# Peripheral_Circuit_B.net
KiCad netlist of a schematic drawn in Altium Designer
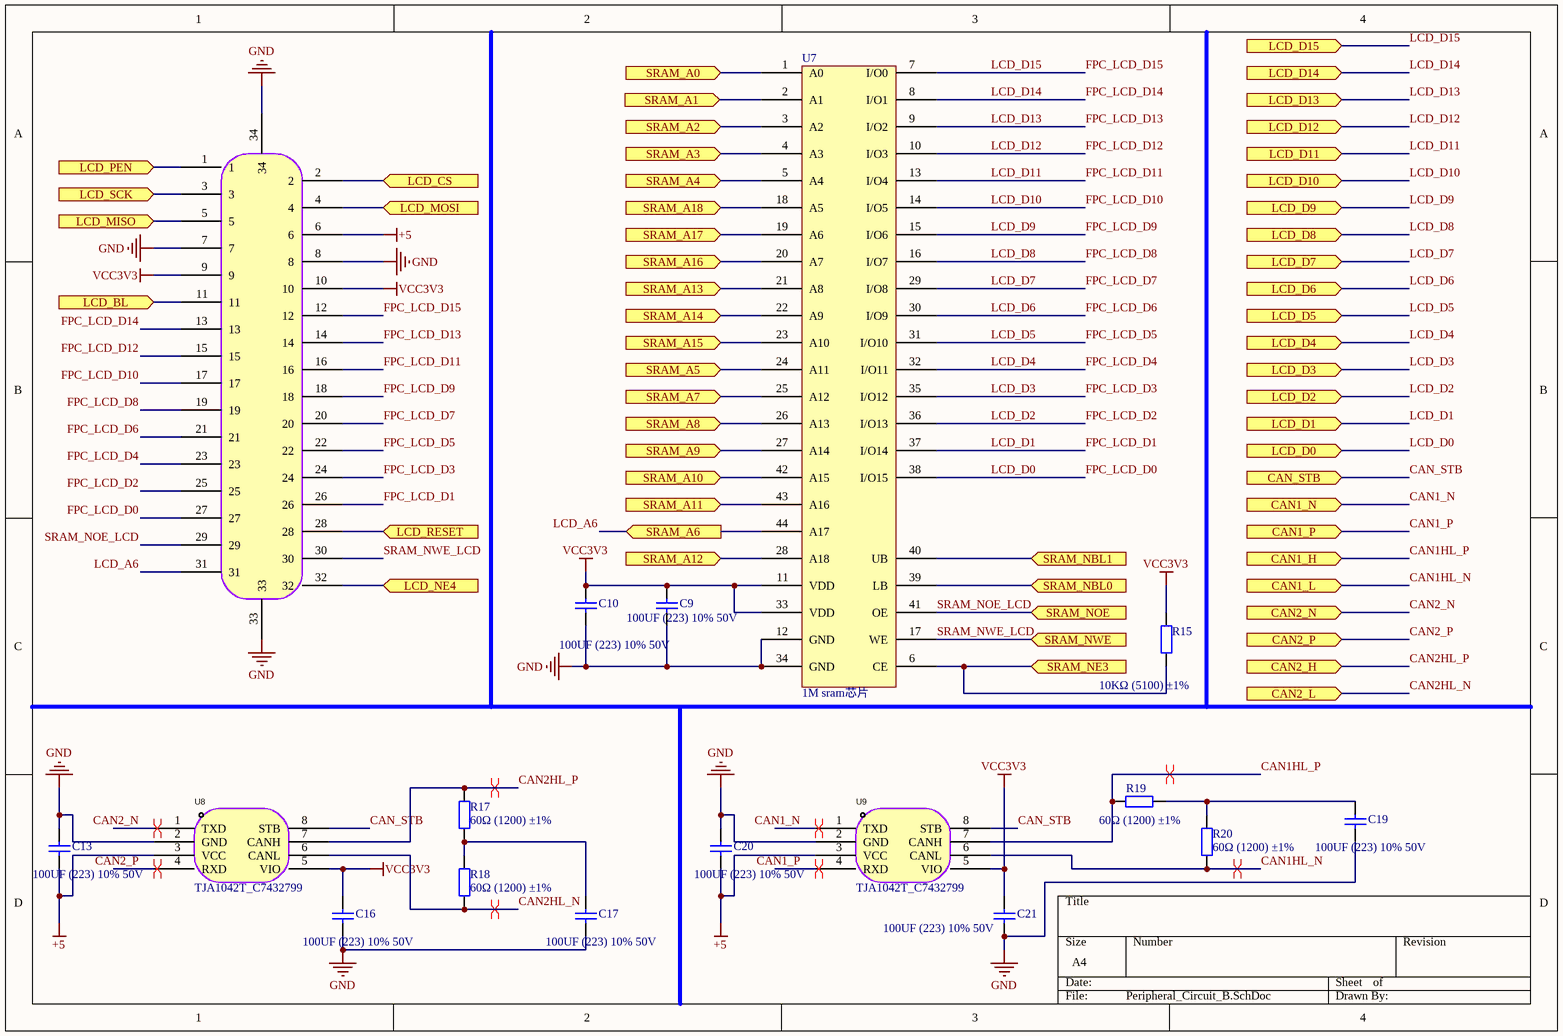
[diagram p0: Peripheral_Circuit_B.SchDoc]

(export (version "E")
  (design (tool "Eeschema 10.0.6"))
  (components
    (comp (ref "C9")
      (value "100UF (223) 10% 50V")
      (footprint "0805_C")
      (description "贴片电容")
      (libsource (lib "Miscellaneous Devices LC") (part "0805 22nF (223) 10% 50V"))
    )
    (comp (ref "C10")
      (value "100UF (223) 10% 50V")
      (footprint "0805_C")
      (description "贴片电容")
      (libsource (lib "Miscellaneous Devices LC") (part "0805 22nF (223) 10% 50V"))
    )
    (comp (ref "C13")
      (value "100UF (223) 10% 50V")
      (footprint "0805_C")
      (description "贴片电容")
      (libsource (lib "Miscellaneous Devices LC") (part "0805 22nF (223) 10% 50V"))
    )
    (comp (ref "C16")
      (value "100UF (223) 10% 50V")
      (footprint "0805_C")
      (description "贴片电容")
      (libsource (lib "Miscellaneous Devices LC") (part "0805 22nF (223) 10% 50V"))
    )
    (comp (ref "C17")
      (value "100UF (223) 10% 50V")
      (footprint "0805_C")
      (description "贴片电容")
      (libsource (lib "Miscellaneous Devices LC") (part "0805 22nF (223) 10% 50V"))
    )
    (comp (ref "C19")
      (value "100UF (223) 10% 50V")
      (footprint "0805_C")
      (description "贴片电容")
      (libsource (lib "Miscellaneous Devices LC") (part "0805 22nF (223) 10% 50V"))
    )
    (comp (ref "C20")
      (value "100UF (223) 10% 50V")
      (footprint "0805_C")
      (description "贴片电容")
      (libsource (lib "Miscellaneous Devices LC") (part "0805 22nF (223) 10% 50V"))
    )
    (comp (ref "C21")
      (value "100UF (223) 10% 50V")
      (footprint "0805_C")
      (description "贴片电容")
      (libsource (lib "Miscellaneous Devices LC") (part "0805 22nF (223) 10% 50V"))
    )
    (comp (ref "FPC1")
      (value "FPC-05F-32PH20")
      (footprint "FPC-SMD_32P-P0.50_XUNPU_FPC-05F-32PH20")
      (fields (field (name "MANUFACTURER") "XUNPU(讯普)"))
      (libsource (lib "EXTRA") (part "FPC-05F-32PH20"))
    )
    (comp (ref "R15")
      (value "10KΩ (5100) ±1%")
      (footprint "0805_R")
      (description "贴片电阻")
      (libsource (lib "Miscellaneous Devices LC") (part "0805 510Ω (5100) 1%"))
    )
    (comp (ref "R17")
      (value "60Ω (1200) ±1%")
      (footprint "0805_R")
      (description "贴片电阻")
      (libsource (lib "") (part "0805 120Ω (1200) 1%_1"))
    )
    (comp (ref "R18")
      (value "60Ω (1200) ±1%")
      (footprint "0805_R")
      (description "贴片电阻")
      (libsource (lib "") (part "0805 120Ω (1200) 1%_1"))
    )
    (comp (ref "R19")
      (value "60Ω (1200) ±1%")
      (footprint "0805_R")
      (description "贴片电阻")
      (libsource (lib "Miscellaneous Devices LC") (part "0805 120Ω (1200) 1%"))
    )
    (comp (ref "R20")
      (value "60Ω (1200) ±1%")
      (footprint "0805_R")
      (description "贴片电阻")
      (libsource (lib "") (part "0805 120Ω (1200) 1%_1"))
    )
    (comp (ref "U7")
      (value "1M sram芯片")
      (footprint "IS61LV51216")
      (description "外接SRAM芯片")
      (libsource (lib "EXTRA") (part "XM8A51216V33A"))
    )
    (comp (ref "U8")
      (value "TJA1042T_C7432799")
      (footprint "TJA1042")
      (fields (field (name "MANUFACTURER") "Tokmas(托克马斯)") (field (name "MANUFACTURER PART") "TJA1042T"))
      (libsource (lib "EXTRA") (part "TJA1042T_C7432799"))
    )
    (comp (ref "U9")
      (value "TJA1042T_C7432799")
      (footprint "TJA1042")
      (fields (field (name "MANUFACTURER") "Tokmas(托克马斯)") (field (name "MANUFACTURER PART") "TJA1042T"))
      (libsource (lib "EXTRA") (part "TJA1042T_C7432799"))
    )
  )
  (nets
    (net (code "1") (name "+5") (class "Default")
      (node (ref "C13") (pin "1") (pinfunction "1_1") (pintype "passive"))
      (node (ref "C20") (pin "1") (pinfunction "1_1") (pintype "passive"))
      (node (ref "FPC1") (pin "6") (pinfunction "6_6") (pintype "passive"))
      (node (ref "U8") (pin "3") (pinfunction "VCC_3") (pintype "passive"))
      (node (ref "U9") (pin "3") (pinfunction "VCC_3") (pintype "passive"))
    )
    (net (code "2") (name "/CAN1HL_N") (class "Default")
      (node (ref "R20") (pin "1") (pinfunction "1_1") (pintype "passive"))
      (node (ref "U9") (pin "6") (pinfunction "CANL_6") (pintype "passive"))
    )
    (net (code "3") (name "/CAN1HL_P") (class "Default")
      (node (ref "R19") (pin "2") (pinfunction "2_2") (pintype "passive"))
      (node (ref "U9") (pin "7") (pinfunction "CANH_7") (pintype "passive"))
    )
    (net (code "4") (name "/CAN1_N") (class "Default")
      (node (ref "U9") (pin "1") (pinfunction "TXD_1") (pintype "passive"))
    )
    (net (code "5") (name "/CAN1_P") (class "Default")
      (node (ref "U9") (pin "4") (pinfunction "RXD_4") (pintype "passive"))
    )
    (net (code "6") (name "/CAN2HL_N") (class "Default")
      (node (ref "R18") (pin "1") (pinfunction "1_1") (pintype "passive"))
      (node (ref "U8") (pin "6") (pinfunction "CANL_6") (pintype "passive"))
    )
    (net (code "7") (name "/CAN2HL_P") (class "Default")
      (node (ref "R17") (pin "2") (pinfunction "2_2") (pintype "passive"))
      (node (ref "U8") (pin "7") (pinfunction "CANH_7") (pintype "passive"))
    )
    (net (code "8") (name "/CAN2_N") (class "Default")
      (node (ref "U8") (pin "1") (pinfunction "TXD_1") (pintype "passive"))
    )
    (net (code "9") (name "/CAN2_P") (class "Default")
      (node (ref "U8") (pin "4") (pinfunction "RXD_4") (pintype "passive"))
    )
    (net (code "10") (name "/CAN_STB") (class "Default")
      (node (ref "U8") (pin "8") (pinfunction "STB_8") (pintype "passive"))
      (node (ref "U9") (pin "8") (pinfunction "STB_8") (pintype "passive"))
    )
    (net (code "11") (name "/FPC_LCD_D0") (class "Default")
      (node (ref "FPC1") (pin "27") (pinfunction "27_27") (pintype "passive"))
      (node (ref "U7") (pin "38") (pinfunction "I/O15_38") (pintype "passive"))
    )
    (net (code "12") (name "/FPC_LCD_D1") (class "Default")
      (node (ref "FPC1") (pin "26") (pinfunction "26_26") (pintype "passive"))
      (node (ref "U7") (pin "37") (pinfunction "I/O14_37") (pintype "passive"))
    )
    (net (code "13") (name "/FPC_LCD_D2") (class "Default")
      (node (ref "FPC1") (pin "25") (pinfunction "25_25") (pintype "passive"))
      (node (ref "U7") (pin "36") (pinfunction "I/O13_36") (pintype "passive"))
    )
    (net (code "14") (name "/FPC_LCD_D3") (class "Default")
      (node (ref "FPC1") (pin "24") (pinfunction "24_24") (pintype "passive"))
      (node (ref "U7") (pin "35") (pinfunction "I/O12_35") (pintype "passive"))
    )
    (net (code "15") (name "/FPC_LCD_D4") (class "Default")
      (node (ref "FPC1") (pin "23") (pinfunction "23_23") (pintype "passive"))
      (node (ref "U7") (pin "32") (pinfunction "I/O11_32") (pintype "passive"))
    )
    (net (code "16") (name "/FPC_LCD_D5") (class "Default")
      (node (ref "FPC1") (pin "22") (pinfunction "22_22") (pintype "passive"))
      (node (ref "U7") (pin "31") (pinfunction "I/O10_31") (pintype "passive"))
    )
    (net (code "17") (name "/FPC_LCD_D6") (class "Default")
      (node (ref "FPC1") (pin "21") (pinfunction "21_21") (pintype "passive"))
      (node (ref "U7") (pin "30") (pinfunction "I/O9_30") (pintype "passive"))
    )
    (net (code "18") (name "/FPC_LCD_D7") (class "Default")
      (node (ref "FPC1") (pin "20") (pinfunction "20_20") (pintype "passive"))
      (node (ref "U7") (pin "29") (pinfunction "I/O8_29") (pintype "passive"))
    )
    (net (code "19") (name "/FPC_LCD_D8") (class "Default")
      (node (ref "FPC1") (pin "19") (pinfunction "19_19") (pintype "passive"))
      (node (ref "U7") (pin "16") (pinfunction "I/O7_16") (pintype "passive"))
    )
    (net (code "20") (name "/FPC_LCD_D9") (class "Default")
      (node (ref "FPC1") (pin "18") (pinfunction "18_18") (pintype "passive"))
      (node (ref "U7") (pin "15") (pinfunction "I/O6_15") (pintype "passive"))
    )
    (net (code "21") (name "/FPC_LCD_D10") (class "Default")
      (node (ref "FPC1") (pin "17") (pinfunction "17_17") (pintype "passive"))
      (node (ref "U7") (pin "14") (pinfunction "I/O5_14") (pintype "passive"))
    )
    (net (code "22") (name "/FPC_LCD_D11") (class "Default")
      (node (ref "FPC1") (pin "16") (pinfunction "16_16") (pintype "passive"))
      (node (ref "U7") (pin "13") (pinfunction "I/O4_13") (pintype "passive"))
    )
    (net (code "23") (name "/FPC_LCD_D12") (class "Default")
      (node (ref "FPC1") (pin "15") (pinfunction "15_15") (pintype "passive"))
      (node (ref "U7") (pin "10") (pinfunction "I/O3_10") (pintype "passive"))
    )
    (net (code "24") (name "/FPC_LCD_D13") (class "Default")
      (node (ref "FPC1") (pin "14") (pinfunction "14_14") (pintype "passive"))
      (node (ref "U7") (pin "9") (pinfunction "I/O2_9") (pintype "passive"))
    )
    (net (code "25") (name "/FPC_LCD_D14") (class "Default")
      (node (ref "FPC1") (pin "13") (pinfunction "13_13") (pintype "passive"))
      (node (ref "U7") (pin "8") (pinfunction "I/O1_8") (pintype "passive"))
    )
    (net (code "26") (name "/FPC_LCD_D15") (class "Default")
      (node (ref "FPC1") (pin "12") (pinfunction "12_12") (pintype "passive"))
      (node (ref "U7") (pin "7") (pinfunction "I/O0_7") (pintype "passive"))
    )
    (net (code "27") (name "/LCD_A6") (class "Default")
      (node (ref "FPC1") (pin "31") (pinfunction "31_31") (pintype "passive"))
      (node (ref "U7") (pin "44") (pinfunction "A17_44") (pintype "passive"))
    )
    (net (code "28") (name "/LCD_BL") (class "Default")
      (node (ref "FPC1") (pin "11") (pinfunction "11_11") (pintype "passive"))
    )
    (net (code "29") (name "/LCD_CS") (class "Default")
      (node (ref "FPC1") (pin "2") (pinfunction "2_2") (pintype "passive"))
    )
    (net (code "30") (name "/LCD_MISO") (class "Default")
      (node (ref "FPC1") (pin "5") (pinfunction "5_5") (pintype "passive"))
    )
    (net (code "31") (name "/LCD_MOSI") (class "Default")
      (node (ref "FPC1") (pin "4") (pinfunction "4_4") (pintype "passive"))
    )
    (net (code "32") (name "/LCD_NE4") (class "Default")
      (node (ref "FPC1") (pin "32") (pinfunction "32_32") (pintype "passive"))
    )
    (net (code "33") (name "/LCD_PEN") (class "Default")
      (node (ref "FPC1") (pin "1") (pinfunction "1_1") (pintype "passive"))
    )
    (net (code "34") (name "/LCD_RESET") (class "Default")
      (node (ref "FPC1") (pin "28") (pinfunction "28_28") (pintype "passive"))
    )
    (net (code "35") (name "/LCD_SCK") (class "Default")
      (node (ref "FPC1") (pin "3") (pinfunction "3_3") (pintype "passive"))
    )
    (net (code "36") (name "/SRAM_A0") (class "Default")
      (node (ref "U7") (pin "1") (pinfunction "A0_1") (pintype "passive"))
    )
    (net (code "37") (name "/SRAM_A1") (class "Default")
      (node (ref "U7") (pin "2") (pinfunction "A1_2") (pintype "passive"))
    )
    (net (code "38") (name "/SRAM_A2") (class "Default")
      (node (ref "U7") (pin "3") (pinfunction "A2_3") (pintype "passive"))
    )
    (net (code "39") (name "/SRAM_A3") (class "Default")
      (node (ref "U7") (pin "4") (pinfunction "A3_4") (pintype "passive"))
    )
    (net (code "40") (name "/SRAM_A4") (class "Default")
      (node (ref "U7") (pin "5") (pinfunction "A4_5") (pintype "passive"))
    )
    (net (code "41") (name "/SRAM_A5") (class "Default")
      (node (ref "U7") (pin "24") (pinfunction "A11_24") (pintype "passive"))
    )
    (net (code "42") (name "/SRAM_A7") (class "Default")
      (node (ref "U7") (pin "25") (pinfunction "A12_25") (pintype "passive"))
    )
    (net (code "43") (name "/SRAM_A8") (class "Default")
      (node (ref "U7") (pin "26") (pinfunction "A13_26") (pintype "passive"))
    )
    (net (code "44") (name "/SRAM_A9") (class "Default")
      (node (ref "U7") (pin "27") (pinfunction "A14_27") (pintype "passive"))
    )
    (net (code "45") (name "/SRAM_A10") (class "Default")
      (node (ref "U7") (pin "42") (pinfunction "A15_42") (pintype "passive"))
    )
    (net (code "46") (name "/SRAM_A11") (class "Default")
      (node (ref "U7") (pin "43") (pinfunction "A16_43") (pintype "passive"))
    )
    (net (code "47") (name "/SRAM_A12") (class "Default")
      (node (ref "U7") (pin "28") (pinfunction "A18_28") (pintype "passive"))
    )
    (net (code "48") (name "/SRAM_A13") (class "Default")
      (node (ref "U7") (pin "21") (pinfunction "A8_21") (pintype "passive"))
    )
    (net (code "49") (name "/SRAM_A14") (class "Default")
      (node (ref "U7") (pin "22") (pinfunction "A9_22") (pintype "passive"))
    )
    (net (code "50") (name "/SRAM_A15") (class "Default")
      (node (ref "U7") (pin "23") (pinfunction "A10_23") (pintype "passive"))
    )
    (net (code "51") (name "/SRAM_A16") (class "Default")
      (node (ref "U7") (pin "20") (pinfunction "A7_20") (pintype "passive"))
    )
    (net (code "52") (name "/SRAM_A17") (class "Default")
      (node (ref "U7") (pin "19") (pinfunction "A6_19") (pintype "passive"))
    )
    (net (code "53") (name "/SRAM_A18") (class "Default")
      (node (ref "U7") (pin "18") (pinfunction "A5_18") (pintype "passive"))
    )
    (net (code "54") (name "/SRAM_NBL0") (class "Default")
      (node (ref "U7") (pin "39") (pinfunction "LB_39") (pintype "passive"))
    )
    (net (code "55") (name "/SRAM_NBL1") (class "Default")
      (node (ref "U7") (pin "40") (pinfunction "UB_40") (pintype "passive"))
    )
    (net (code "56") (name "/SRAM_NE3") (class "Default")
      (node (ref "R15") (pin "1") (pinfunction "1_1") (pintype "passive"))
      (node (ref "U7") (pin "6") (pinfunction "CE_6") (pintype "passive"))
    )
    (net (code "57") (name "/SRAM_NOE_LCD") (class "Default")
      (node (ref "FPC1") (pin "29") (pinfunction "29_29") (pintype "passive"))
      (node (ref "U7") (pin "41") (pinfunction "OE_41") (pintype "passive"))
    )
    (net (code "58") (name "/SRAM_NWE_LCD") (class "Default")
      (node (ref "FPC1") (pin "30") (pinfunction "30_30") (pintype "passive"))
      (node (ref "U7") (pin "17") (pinfunction "WE_17") (pintype "passive"))
    )
    (net (code "59") (name "GND") (class "Default")
      (node (ref "C10") (pin "1") (pinfunction "1_1") (pintype "passive"))
      (node (ref "C13") (pin "2") (pinfunction "2_2") (pintype "passive"))
      (node (ref "C16") (pin "1") (pinfunction "1_1") (pintype "passive"))
      (node (ref "C17") (pin "1") (pinfunction "1_1") (pintype "passive"))
      (node (ref "C19") (pin "1") (pinfunction "1_1") (pintype "passive"))
      (node (ref "C20") (pin "2") (pinfunction "2_2") (pintype "passive"))
      (node (ref "C21") (pin "1") (pinfunction "1_1") (pintype "passive"))
      (node (ref "C9") (pin "1") (pinfunction "1_1") (pintype "passive"))
      (node (ref "FPC1") (pin "33") (pinfunction "33_33") (pintype "passive"))
      (node (ref "FPC1") (pin "34") (pinfunction "34_34") (pintype "passive"))
      (node (ref "FPC1") (pin "7") (pinfunction "7_7") (pintype "passive"))
      (node (ref "FPC1") (pin "8") (pinfunction "8_8") (pintype "passive"))
      (node (ref "U7") (pin "12") (pinfunction "GND_12") (pintype "passive"))
      (node (ref "U7") (pin "34") (pinfunction "GND_34") (pintype "passive"))
      (node (ref "U8") (pin "2") (pinfunction "GND_2") (pintype "passive"))
      (node (ref "U9") (pin "2") (pinfunction "GND_2") (pintype "passive"))
    )
    (net (code "60") (name "Net-(C17-Pad2)") (class "Default")
      (node (ref "C17") (pin "2") (pinfunction "2_2") (pintype "passive"))
      (node (ref "R17") (pin "1") (pinfunction "1_1") (pintype "passive"))
      (node (ref "R18") (pin "2") (pinfunction "2_2") (pintype "passive"))
    )
    (net (code "61") (name "Net-(C19-Pad2)") (class "Default")
      (node (ref "C19") (pin "2") (pinfunction "2_2") (pintype "passive"))
      (node (ref "R19") (pin "1") (pinfunction "1_1") (pintype "passive"))
      (node (ref "R20") (pin "2") (pinfunction "2_2") (pintype "passive"))
    )
    (net (code "62") (name "VCC3V3") (class "Default")
      (node (ref "C10") (pin "2") (pinfunction "2_2") (pintype "passive"))
      (node (ref "C16") (pin "2") (pinfunction "2_2") (pintype "passive"))
      (node (ref "C21") (pin "2") (pinfunction "2_2") (pintype "passive"))
      (node (ref "C9") (pin "2") (pinfunction "2_2") (pintype "passive"))
      (node (ref "FPC1") (pin "10") (pinfunction "10_10") (pintype "passive"))
      (node (ref "FPC1") (pin "9") (pinfunction "9_9") (pintype "passive"))
      (node (ref "R15") (pin "2") (pinfunction "2_2") (pintype "passive"))
      (node (ref "U7") (pin "11") (pinfunction "VDD_11") (pintype "passive"))
      (node (ref "U7") (pin "33") (pinfunction "VDD_33") (pintype "passive"))
      (node (ref "U8") (pin "5") (pinfunction "VIO_5") (pintype "passive"))
      (node (ref "U9") (pin "5") (pinfunction "VIO_5") (pintype "passive"))
    )
  )
)
